# Motoransteurung.net
KiCad netlist of a schematic drawn in Altium Designer
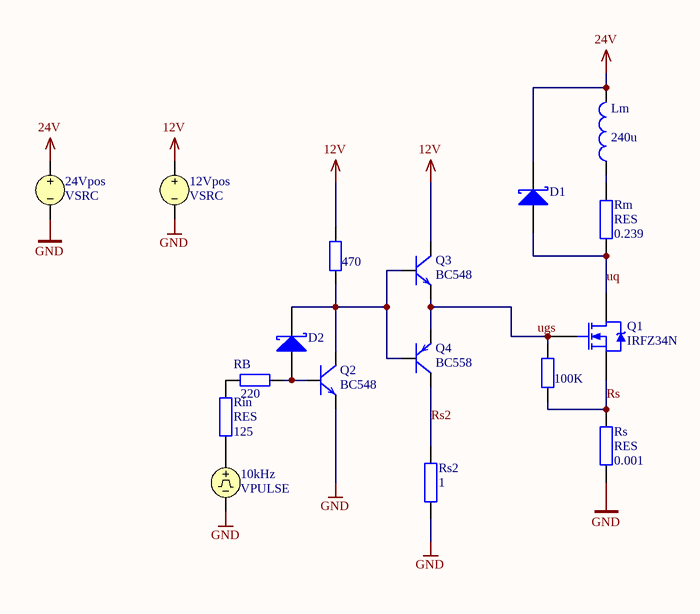
[diagram p0: Motoransteurung.SchDoc]

(export (version "E")
  (design (tool "Eeschema 10.0.6"))
  (components
    (comp (ref "10kHz")
      (value "VPULSE")
      (description "Pulse Voltage Source")
      (fields (field (name "PUBLISHER") "Altium Limited"))
      (libsource (lib "Simulation Sources") (part "VPULSE"))
    )
    (comp (ref "12Vpos")
      (value "VSRC")
      (description "Voltage Source")
      (fields (field (name "PUBLISHER") "Altium Limited"))
      (libsource (lib "Simulation Sources") (part "VSRC"))
    )
    (comp (ref "24Vpos")
      (value "VSRC")
      (description "Voltage Source")
      (fields (field (name "PUBLISHER") "Altium Limited"))
      (libsource (lib "Simulation Sources") (part "VSRC"))
    )
    (comp (ref "D1")
      (value "DSchottky")
      (footprint "DIODE-0.4/085")
      (description "Schottky Diode")
      (fields (field (name "PUBLISHER") "Altium Limited"))
      (libsource (lib "Miscellaneous Devices") (part "D Schottky"))
    )
    (comp (ref "D2")
      (value "D Schottky")
      (footprint "DIODE-0.4/085")
      (description "Schottky Diode")
      (fields (field (name "PUBLISHER") "Altium Limited"))
      (libsource (lib "Miscellaneous Devices") (part "D Schottky"))
    )
    (comp (ref "Lm")
      (value "240u")
      (footprint "0402-A")
      (description "Inductor")
      (fields (field (name "PUBLISHER") "Altium Limited"))
      (libsource (lib "Miscellaneous Devices") (part "Inductor"))
    )
    (comp (ref "Q1")
      (value "IRFZ34N")
      (footprint "TO-220AB")
      (description "HEXFET Power MOSFET")
      (fields (field (name "PUBLISHER") "Altium Limited"))
      (libsource (lib "IR Discrete MOSFET - Power") (part "IRFZ34N"))
    )
    (comp (ref "Q2")
      (value "BC548")
      (footprint "TO-92/EBC")
      (description "Transistor")
      (libsource (lib "Sode-Sym") (part "NPN"))
    )
    (comp (ref "Q3")
      (value "BC548")
      (footprint "TO-92/EBC")
      (description "Transistor")
      (libsource (lib "Sode-Sym") (part "NPN"))
    )
    (comp (ref "Q4")
      (value "BC558")
      (footprint "TO-92/EBC")
      (description "Transistor")
      (libsource (lib "Sode-Sym") (part "PNP"))
    )
    (comp (ref "R3")
      (value "470")
      (footprint "AXIAL-0.4")
      (description "Resistor")
      (fields (field (name "Comment") "Res2") (field (name "PUBLISHER") "Altium Limited"))
      (libsource (lib "Miscellaneous Devices") (part "Res2"))
    )
    (comp (ref "R7")
      (value "100K")
      (footprint "AXIAL-0.4")
      (description "Resistor")
      (fields (field (name "Comment") "Res2") (field (name "PUBLISHER") "Altium Limited"))
      (libsource (lib "Miscellaneous Devices") (part "Res2"))
    )
    (comp (ref "RB")
      (value "220")
      (footprint "AXIAL-0.4")
      (description "Resistor")
      (fields (field (name "Comment") "Res2") (field (name "PUBLISHER") "Altium Limited"))
      (libsource (lib "") (part "Res2_1"))
    )
    (comp (ref "Rin")
      (value "RES")
      (footprint "Axial-0.4")
      (description "Widerstand")
      (fields (field (name "ALTIUM_VALUE") "125"))
      (libsource (lib "Sode-Sym") (part "RES"))
    )
    (comp (ref "Rm")
      (value "RES")
      (footprint "Axial-0.4")
      (description "Widerstand")
      (fields (field (name "ALTIUM_VALUE") "0.239"))
      (libsource (lib "Sode-Sym") (part "RES"))
    )
    (comp (ref "Rs")
      (value "RES")
      (footprint "Axial-0.4")
      (description "Widerstand")
      (fields (field (name "ALTIUM_VALUE") "0.001"))
      (libsource (lib "Sode-Sym") (part "RES"))
    )
    (comp (ref "Rs2")
      (value "1")
      (footprint "Axial-0.4")
      (description "Widerstand")
      (fields (field (name "Comment") "RES"))
      (libsource (lib "Sode-Sym") (part "RES"))
    )
  )
  (nets
    (net (code "1") (name "/Rs") (class "Default")
      (node (ref "Q1") (pin "3") (pinfunction "S_3") (pintype "passive"))
      (node (ref "R7") (pin "2") (pinfunction "2_2") (pintype "passive"))
      (node (ref "Rs") (pin "1") (pintype "passive"))
    )
    (net (code "2") (name "/Rs2") (class "Default")
      (node (ref "Q4") (pin "3") (pinfunction "C_3") (pintype "passive"))
      (node (ref "Rs2") (pin "1") (pintype "passive"))
    )
    (net (code "3") (name "/ugs") (class "Default")
      (node (ref "Q1") (pin "1") (pinfunction "G_1") (pintype "passive"))
      (node (ref "Q3") (pin "2") (pinfunction "E_2") (pintype "passive"))
      (node (ref "Q4") (pin "2") (pinfunction "E_2") (pintype "passive"))
      (node (ref "R7") (pin "1") (pinfunction "1_1") (pintype "passive"))
    )
    (net (code "4") (name "/uq") (class "Default")
      (node (ref "D1") (pin "1") (pinfunction "A_1") (pintype "passive"))
      (node (ref "Q1") (pin "2") (pinfunction "D_2") (pintype "passive"))
      (node (ref "Rm") (pin "1") (pintype "passive"))
    )
    (net (code "5") (name "12V") (class "Default")
      (node (ref "12Vpos") (pin "1") (pinfunction "1_1") (pintype "passive"))
      (node (ref "Q3") (pin "3") (pinfunction "C_3") (pintype "passive"))
      (node (ref "R3") (pin "1") (pinfunction "1_1") (pintype "passive"))
    )
    (net (code "6") (name "24V") (class "Default")
      (node (ref "24Vpos") (pin "1") (pinfunction "1_1") (pintype "passive"))
      (node (ref "D1") (pin "2") (pinfunction "K_2") (pintype "passive"))
      (node (ref "Lm") (pin "2") (pinfunction "2_2") (pintype "passive"))
    )
    (net (code "7") (name "GND") (class "Default")
      (node (ref "10kHz") (pin "2") (pinfunction "2_2") (pintype "passive"))
      (node (ref "12Vpos") (pin "2") (pinfunction "2_2") (pintype "passive"))
      (node (ref "Q2") (pin "2") (pinfunction "E_2") (pintype "passive"))
      (node (ref "Rs") (pin "2") (pintype "passive"))
      (node (ref "Rs2") (pin "2") (pintype "passive"))
    )
    (net (code "8") (name "Net-(10kHz-Pad1)") (class "Default")
      (node (ref "10kHz") (pin "1") (pinfunction "1_1") (pintype "passive"))
      (node (ref "Rin") (pin "1") (pintype "passive"))
    )
    (net (code "9") (name "Net-(D2-A)") (class "Default")
      (node (ref "D2") (pin "1") (pinfunction "A_1") (pintype "passive"))
      (node (ref "Q2") (pin "1") (pinfunction "B_1") (pintype "passive"))
      (node (ref "RB") (pin "1") (pinfunction "1_1") (pintype "passive"))
    )
    (net (code "10") (name "Net-(D2-K)") (class "Default")
      (node (ref "D2") (pin "2") (pinfunction "K_2") (pintype "passive"))
      (node (ref "Q2") (pin "3") (pinfunction "C_3") (pintype "passive"))
      (node (ref "Q3") (pin "1") (pinfunction "B_1") (pintype "passive"))
      (node (ref "Q4") (pin "1") (pinfunction "B_1") (pintype "passive"))
      (node (ref "R3") (pin "2") (pinfunction "2_2") (pintype "passive"))
    )
    (net (code "11") (name "Net-(Lm-Pad1)") (class "Default")
      (node (ref "Lm") (pin "1") (pinfunction "1_1") (pintype "passive"))
      (node (ref "Rm") (pin "2") (pintype "passive"))
    )
    (net (code "12") (name "Net-(RB-Pad2)") (class "Default")
      (node (ref "RB") (pin "2") (pinfunction "2_2") (pintype "passive"))
      (node (ref "Rin") (pin "2") (pintype "passive"))
    )
    (net (code "13") (name "unconnected-(24Vpos-Pad2)") (class "Default")
      (node (ref "24Vpos") (pin "2") (pinfunction "2_2") (pintype "passive"))
    )
  )
)
